# Camera_board.net
KiCad netlist of a schematic drawn in EAGLE
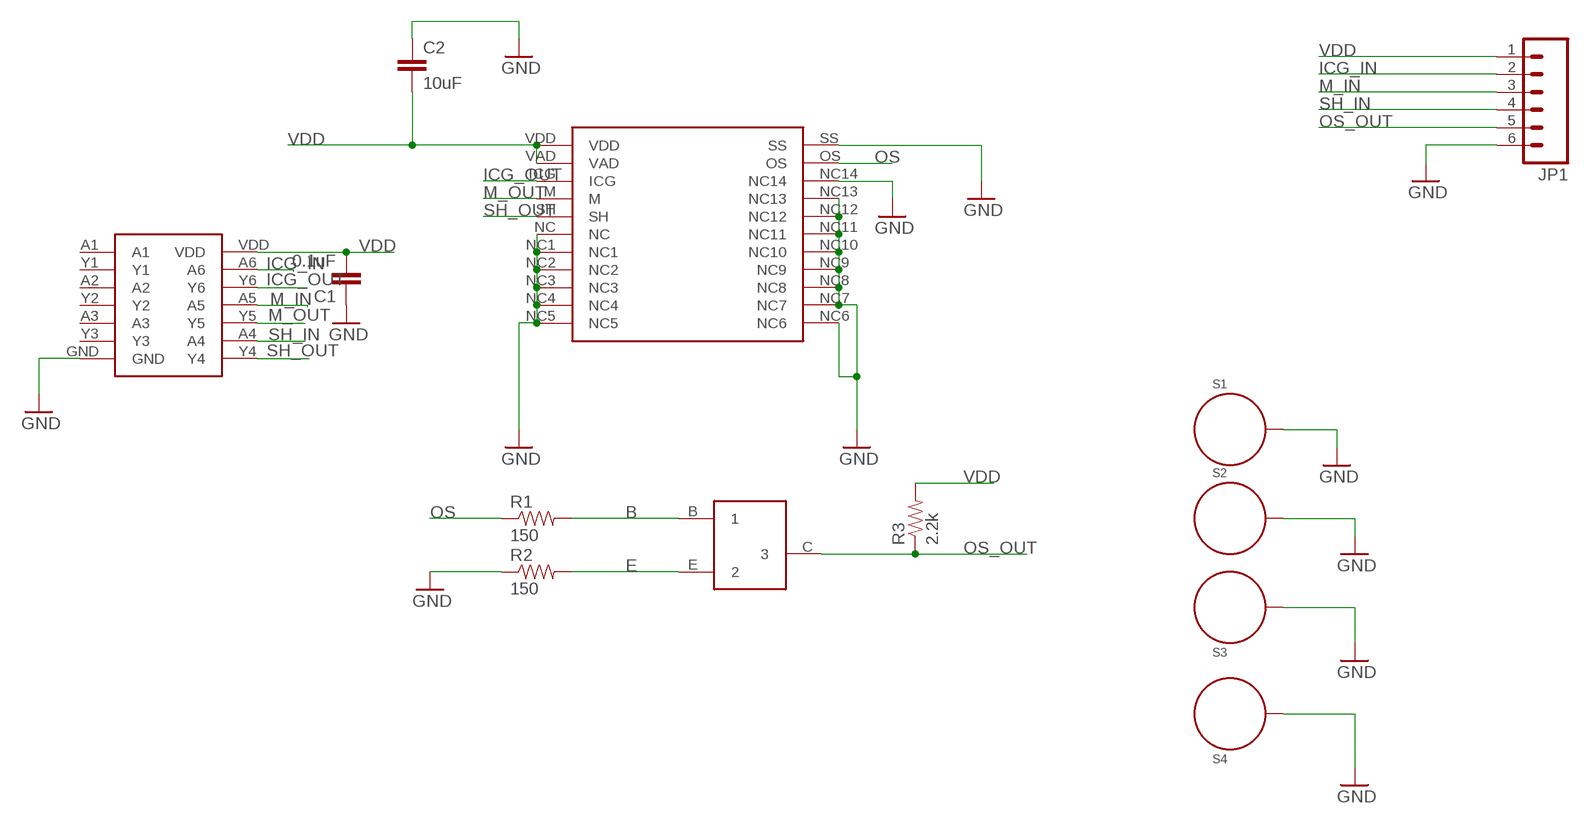
[diagram p0: schematic, sheet 1]

(export (version "E")
  (design (tool "Eeschema 10.0.6"))
  (components
    (comp (ref "C1")
      (value "0.1uF")
      (footprint "eagle-import:1206")
      (libsource (lib "eagle-import") (part "CAP1206"))
    )
    (comp (ref "C2")
      (value "10uF")
      (footprint "eagle-import:1206")
      (libsource (lib "eagle-import") (part "CAP1206"))
    )
    (comp (ref "JP1")
      (value "M06POLAR")
      (footprint "eagle-import:MOLEX-1X6")
      (libsource (lib "eagle-import") (part "M06POLAR"))
    )
    (comp (ref "R1")
      (value "150")
      (footprint "eagle-import:1206")
      (libsource (lib "eagle-import") (part "RESISTOR1206"))
    )
    (comp (ref "R2")
      (value "150")
      (footprint "eagle-import:1206")
      (libsource (lib "eagle-import") (part "RESISTOR1206"))
    )
    (comp (ref "R3")
      (value "2.2k")
      (footprint "eagle-import:1206")
      (libsource (lib "eagle-import") (part "RESISTOR1206"))
    )
    (comp (ref "S1")
      (value "STANDOFF_ELECTRICAL")
      (footprint "eagle-import:STANDOFF-ELECTRICAL")
      (libsource (lib "eagle-import") (part "STANDOFF_ELECTRICAL"))
    )
    (comp (ref "S2")
      (value "STANDOFF_ELECTRICAL")
      (footprint "eagle-import:STANDOFF-ELECTRICAL")
      (libsource (lib "eagle-import") (part "STANDOFF_ELECTRICAL"))
    )
    (comp (ref "S3")
      (value "STANDOFF_ELECTRICAL")
      (footprint "eagle-import:STANDOFF-ELECTRICAL")
      (libsource (lib "eagle-import") (part "STANDOFF_ELECTRICAL"))
    )
    (comp (ref "S4")
      (value "STANDOFF_ELECTRICAL")
      (footprint "eagle-import:STANDOFF-ELECTRICAL")
      (libsource (lib "eagle-import") (part "STANDOFF_ELECTRICAL"))
    )
    (comp (ref "U$1")
      (value "TRANSISTOR")
      (footprint "eagle-import:SOT23-BEC")
      (libsource (lib "eagle-import") (part "TRANSISTOR"))
    )
    (comp (ref "U$2")
      (value "CCDCAMERA")
      (footprint "eagle-import:CCDCAMERA")
      (libsource (lib "eagle-import") (part "CCDCAMERA"))
    )
    (comp (ref "U$3")
      (value "CMOS_HEX_INVERTER")
      (footprint "eagle-import:CMOS_HEX_INVERTER")
      (libsource (lib "eagle-import") (part "CMOS_HEX_INVERTER"))
    )
  )
  (nets
    (net (code "1") (name "/B") (class "Default")
      (node (ref "R1") (pin "2") (pinfunction "2_2") (pintype "passive"))
      (node (ref "U$1") (pin "B") (pinfunction "1_B") (pintype "bidirectional"))
    )
    (net (code "2") (name "/E") (class "Default")
      (node (ref "R2") (pin "2") (pinfunction "2_2") (pintype "passive"))
      (node (ref "U$1") (pin "E") (pinfunction "2_E") (pintype "bidirectional"))
    )
    (net (code "3") (name "/ICG_IN") (class "Default")
      (node (ref "JP1") (pin "2") (pinfunction "2_2") (pintype "passive"))
      (node (ref "U$3") (pin "A6") (pinfunction "A6_A6") (pintype "bidirectional"))
    )
    (net (code "4") (name "/ICG_OUT") (class "Default")
      (node (ref "U$2") (pin "ICG") (pinfunction "ICG_ICG") (pintype "bidirectional"))
      (node (ref "U$3") (pin "Y6") (pinfunction "Y6_Y6") (pintype "bidirectional"))
    )
    (net (code "5") (name "/M_IN") (class "Default")
      (node (ref "JP1") (pin "3") (pinfunction "3_3") (pintype "passive"))
      (node (ref "U$3") (pin "A5") (pinfunction "A5_A5") (pintype "bidirectional"))
    )
    (net (code "6") (name "/M_OUT") (class "Default")
      (node (ref "U$2") (pin "M") (pinfunction "M_M") (pintype "bidirectional"))
      (node (ref "U$3") (pin "Y5") (pinfunction "Y5_Y5") (pintype "bidirectional"))
    )
    (net (code "7") (name "/OS") (class "Default")
      (node (ref "R1") (pin "1") (pinfunction "1_1") (pintype "passive"))
      (node (ref "U$2") (pin "OS") (pinfunction "OS_OS") (pintype "bidirectional"))
    )
    (net (code "8") (name "/OS_OUT") (class "Default")
      (node (ref "JP1") (pin "5") (pinfunction "5_5") (pintype "passive"))
      (node (ref "R3") (pin "1") (pinfunction "1_1") (pintype "passive"))
      (node (ref "U$1") (pin "C") (pinfunction "3_C") (pintype "bidirectional"))
    )
    (net (code "9") (name "/SH_IN") (class "Default")
      (node (ref "JP1") (pin "4") (pinfunction "4_4") (pintype "passive"))
      (node (ref "U$3") (pin "A4") (pinfunction "A4_A4") (pintype "bidirectional"))
    )
    (net (code "10") (name "/SH_OUT") (class "Default")
      (node (ref "U$2") (pin "SH") (pinfunction "SH_SH") (pintype "bidirectional"))
      (node (ref "U$3") (pin "Y4") (pinfunction "Y4_Y4") (pintype "bidirectional"))
    )
    (net (code "11") (name "/VDD") (class "Default")
      (node (ref "C1") (pin "2") (pinfunction "2_2") (pintype "passive"))
      (node (ref "C2") (pin "2") (pinfunction "2_2") (pintype "passive"))
      (node (ref "JP1") (pin "1") (pinfunction "1_1") (pintype "passive"))
      (node (ref "R3") (pin "2") (pinfunction "2_2") (pintype "passive"))
      (node (ref "U$2") (pin "VAD") (pinfunction "VAD_VAD") (pintype "bidirectional"))
      (node (ref "U$2") (pin "VDD") (pinfunction "VDD_VDD") (pintype "bidirectional"))
      (node (ref "U$3") (pin "VDD") (pinfunction "VDD_VDD") (pintype "bidirectional"))
    )
    (net (code "12") (name "GND") (class "Default")
      (node (ref "C1") (pin "1") (pinfunction "1_1") (pintype "passive"))
      (node (ref "C2") (pin "1") (pinfunction "1_1") (pintype "passive"))
      (node (ref "JP1") (pin "6") (pinfunction "6_6") (pintype "passive"))
      (node (ref "R2") (pin "1") (pinfunction "1_1") (pintype "passive"))
      (node (ref "S1") (pin "P1") (pinfunction "P$1_P1") (pintype "bidirectional"))
      (node (ref "S2") (pin "P1") (pinfunction "P$1_P1") (pintype "bidirectional"))
      (node (ref "S3") (pin "P1") (pinfunction "P$1_P1") (pintype "bidirectional"))
      (node (ref "S4") (pin "P1") (pinfunction "P$1_P1") (pintype "bidirectional"))
      (node (ref "U$2") (pin "NC") (pinfunction "NC_NC") (pintype "bidirectional"))
      (node (ref "U$2") (pin "NC1") (pinfunction "NC1_NC1") (pintype "bidirectional"))
      (node (ref "U$2") (pin "NC10") (pinfunction "NC10_NC10") (pintype "bidirectional"))
      (node (ref "U$2") (pin "NC11") (pinfunction "NC11_NC11") (pintype "bidirectional"))
      (node (ref "U$2") (pin "NC12") (pinfunction "NC12_NC12") (pintype "bidirectional"))
      (node (ref "U$2") (pin "NC13") (pinfunction "NC13_NC13") (pintype "bidirectional"))
      (node (ref "U$2") (pin "NC14") (pinfunction "NC14_NC14") (pintype "bidirectional"))
      (node (ref "U$2") (pin "NC2") (pinfunction "NC2_NC2") (pintype "bidirectional"))
      (node (ref "U$2") (pin "NC3") (pinfunction "NC3_NC3") (pintype "bidirectional"))
      (node (ref "U$2") (pin "NC4") (pinfunction "NC4_NC4") (pintype "bidirectional"))
      (node (ref "U$2") (pin "NC5") (pinfunction "NC5_NC5") (pintype "bidirectional"))
      (node (ref "U$2") (pin "NC6") (pinfunction "NC6_NC6") (pintype "bidirectional"))
      (node (ref "U$2") (pin "NC7") (pinfunction "NC7_NC7") (pintype "bidirectional"))
      (node (ref "U$2") (pin "NC8") (pinfunction "NC8_NC8") (pintype "bidirectional"))
      (node (ref "U$2") (pin "NC9") (pinfunction "NC9_NC9") (pintype "bidirectional"))
      (node (ref "U$2") (pin "SS") (pinfunction "SS_SS") (pintype "bidirectional"))
      (node (ref "U$3") (pin "GND") (pinfunction "GND_GND") (pintype "bidirectional"))
    )
    (net (code "13") (name "unconnected-(U$3-PadA1)") (class "Default")
      (node (ref "U$3") (pin "A1") (pinfunction "A1_A1") (pintype "bidirectional"))
    )
    (net (code "14") (name "unconnected-(U$3-PadA2)") (class "Default")
      (node (ref "U$3") (pin "A2") (pinfunction "A2_A2") (pintype "bidirectional"))
    )
    (net (code "15") (name "unconnected-(U$3-PadA3)") (class "Default")
      (node (ref "U$3") (pin "A3") (pinfunction "A3_A3") (pintype "bidirectional"))
    )
    (net (code "16") (name "unconnected-(U$3-PadY1)") (class "Default")
      (node (ref "U$3") (pin "Y1") (pinfunction "Y1_Y1") (pintype "bidirectional"))
    )
    (net (code "17") (name "unconnected-(U$3-PadY2)") (class "Default")
      (node (ref "U$3") (pin "Y2") (pinfunction "Y2_Y2") (pintype "bidirectional"))
    )
    (net (code "18") (name "unconnected-(U$3-PadY3)") (class "Default")
      (node (ref "U$3") (pin "Y3") (pinfunction "Y3_Y3") (pintype "bidirectional"))
    )
  )
)
